# control.net
KiCad netlist of a schematic drawn in EAGLE
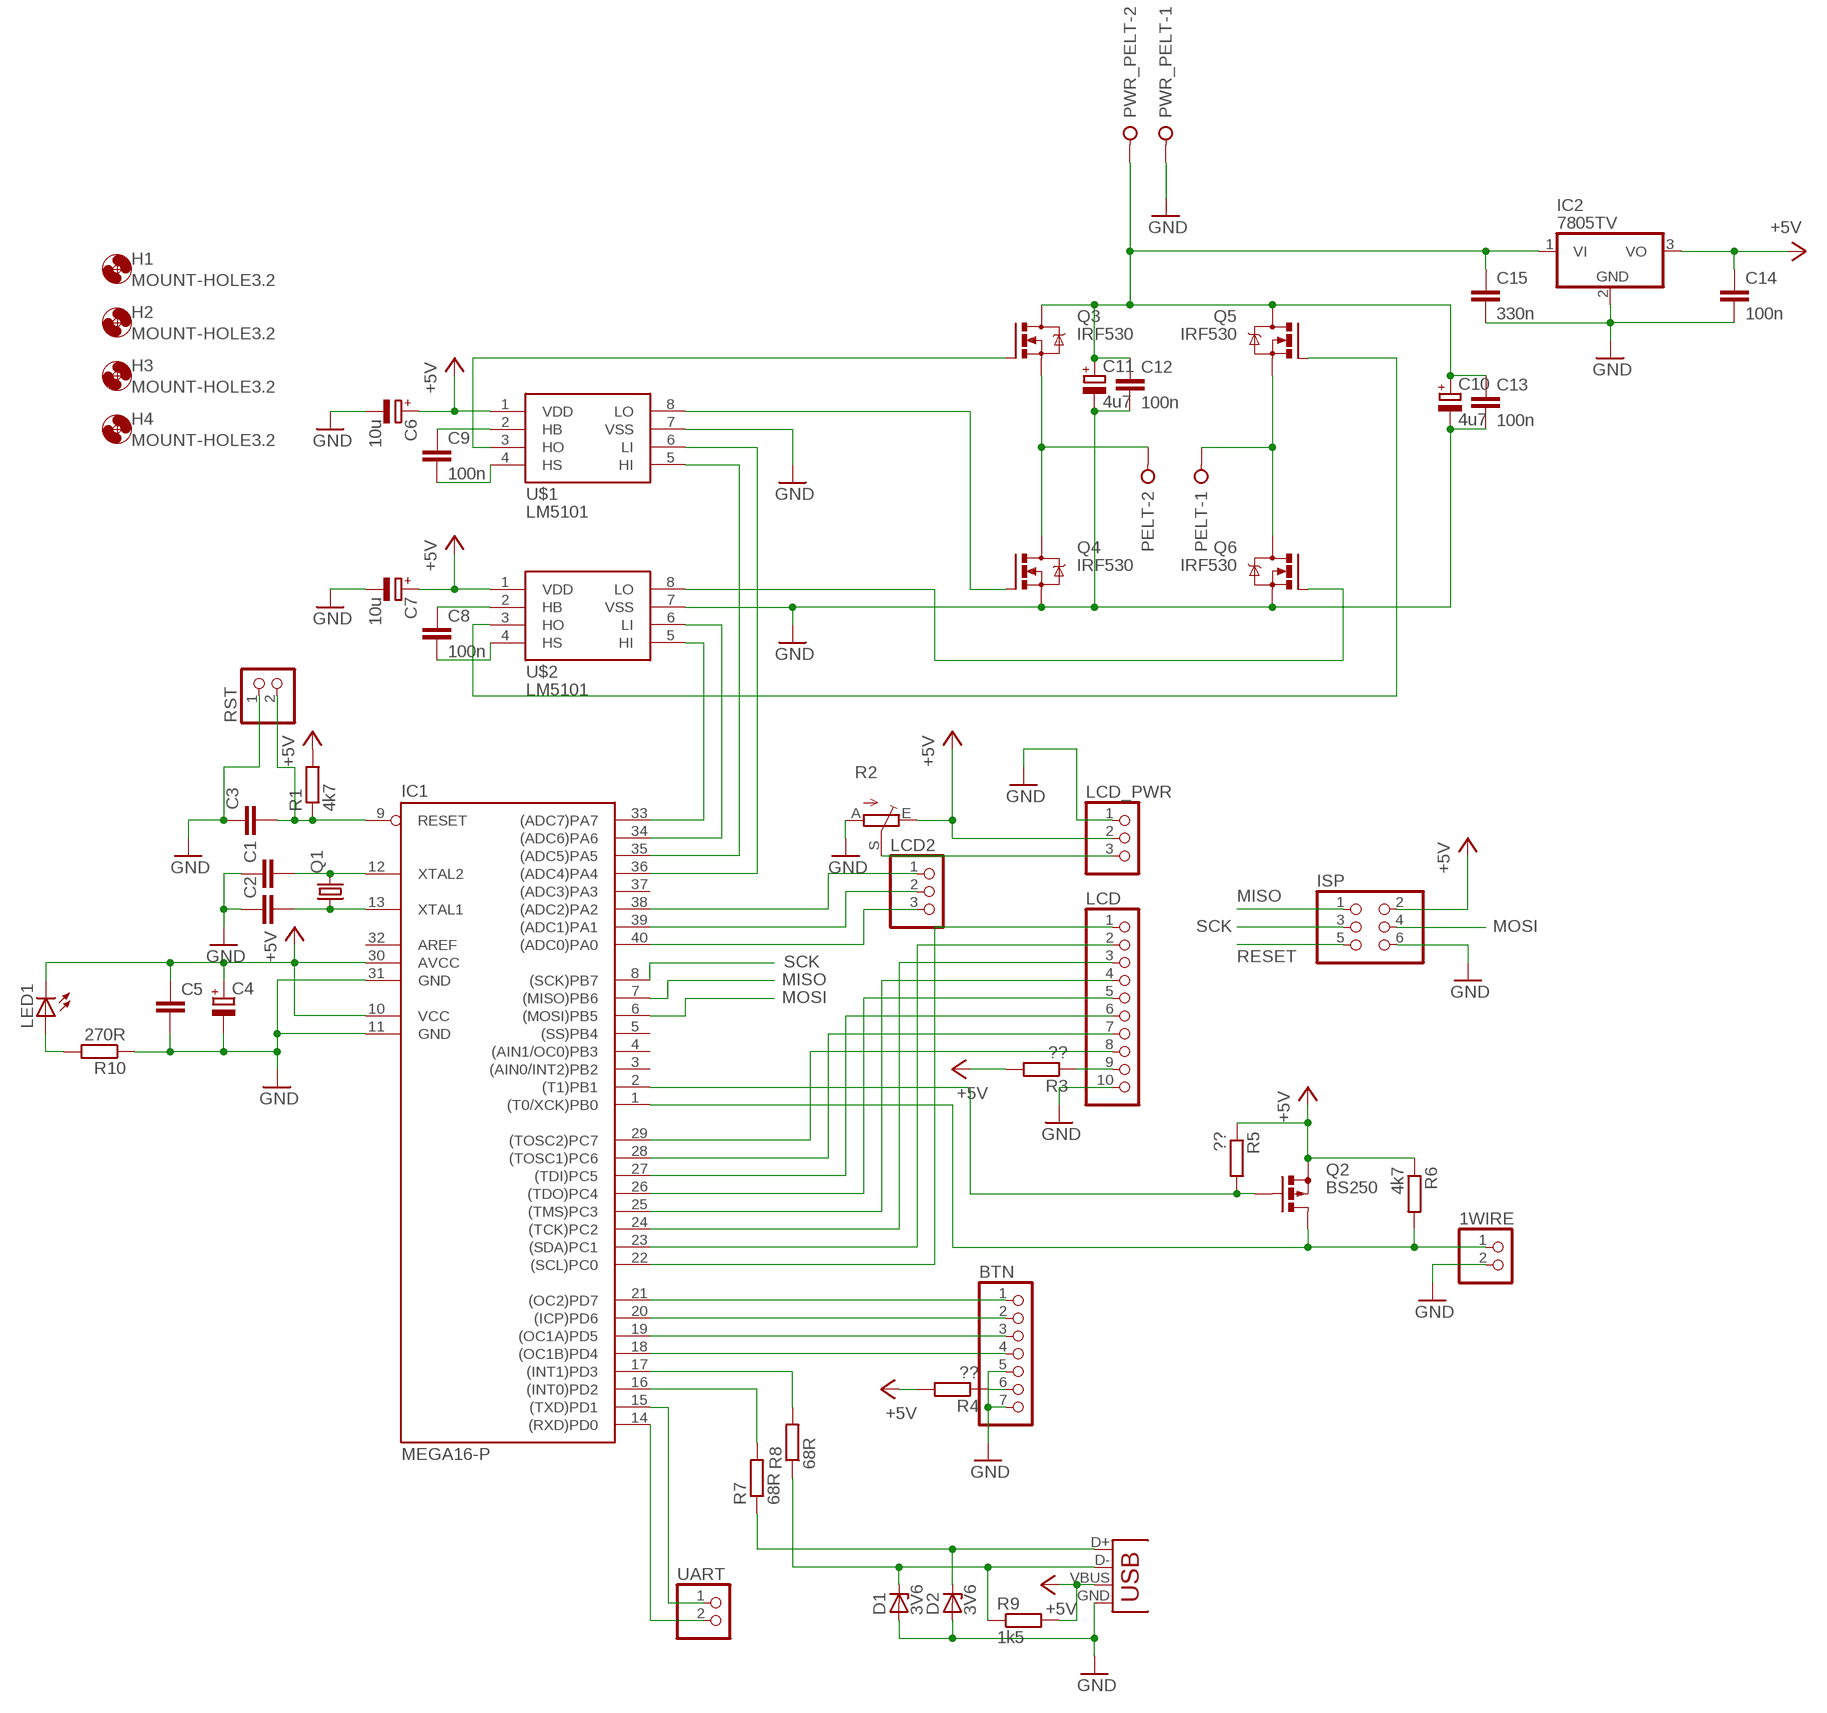
[diagram p0: schematic, sheet 1]

(export (version "E")
  (design (tool "Eeschema 10.0.6"))
  (components
    (comp (ref "1WIRE")
      (value "PINHD-1X2")
      (footprint "eagle-import:1X02")
      (libsource (lib "eagle-import") (part "PINHD-1X2"))
    )
    (comp (ref "BTN")
      (value "PINHD-1X7")
      (footprint "eagle-import:1X07")
      (libsource (lib "eagle-import") (part "PINHD-1X7"))
    )
    (comp (ref "C1")
      (value "C-EU025-025X050")
      (footprint "eagle-import:C025-025X050")
      (libsource (lib "eagle-import") (part "C-EU025-025X050"))
    )
    (comp (ref "C2")
      (value "C-EU025-025X050")
      (footprint "eagle-import:C025-025X050")
      (libsource (lib "eagle-import") (part "C-EU025-025X050"))
    )
    (comp (ref "C3")
      (value "C-EU050-024X044")
      (footprint "eagle-import:C050-024X044")
      (libsource (lib "eagle-import") (part "C-EU050-024X044"))
    )
    (comp (ref "C4")
      (value "CPOL-EUE2.5-5")
      (footprint "eagle-import:E2,5-5")
      (libsource (lib "eagle-import") (part "CPOL-EUE2.5-5"))
    )
    (comp (ref "C5")
      (value "C-EU050-024X044")
      (footprint "eagle-import:C050-024X044")
      (libsource (lib "eagle-import") (part "C-EU050-024X044"))
    )
    (comp (ref "C6")
      (value "10u")
      (footprint "eagle-import:E2,5-5")
      (libsource (lib "eagle-import") (part "CPOL-EUE2.5-5"))
    )
    (comp (ref "C7")
      (value "10u")
      (footprint "eagle-import:E2,5-5")
      (libsource (lib "eagle-import") (part "CPOL-EUE2.5-5"))
    )
    (comp (ref "C8")
      (value "100n")
      (footprint "eagle-import:C025-025X050")
      (libsource (lib "eagle-import") (part "C-EU025-025X050"))
    )
    (comp (ref "C9")
      (value "100n")
      (footprint "eagle-import:C025-025X050")
      (libsource (lib "eagle-import") (part "C-EU025-025X050"))
    )
    (comp (ref "C10")
      (value "4u7")
      (footprint "eagle-import:E5-5")
      (libsource (lib "eagle-import") (part "CPOL-EUE5-5"))
    )
    (comp (ref "C11")
      (value "4u7")
      (footprint "eagle-import:E5-5")
      (libsource (lib "eagle-import") (part "CPOL-EUE5-5"))
    )
    (comp (ref "C12")
      (value "100n")
      (footprint "eagle-import:C025-025X050")
      (libsource (lib "eagle-import") (part "C-EU025-025X050"))
    )
    (comp (ref "C13")
      (value "100n")
      (footprint "eagle-import:C025-025X050")
      (libsource (lib "eagle-import") (part "C-EU025-025X050"))
    )
    (comp (ref "C14")
      (value "100n")
      (footprint "eagle-import:C025-025X050")
      (libsource (lib "eagle-import") (part "C-EU025-025X050"))
    )
    (comp (ref "C15")
      (value "330n")
      (footprint "eagle-import:C025-025X050")
      (libsource (lib "eagle-import") (part "C-EU025-025X050"))
    )
    (comp (ref "D1")
      (value "3V6")
      (footprint "eagle-import:ZDIO-7.5")
      (libsource (lib "eagle-import") (part "ZENER-DIODEZD-7.5"))
    )
    (comp (ref "D2")
      (value "3V6")
      (footprint "eagle-import:ZDIO-7.5")
      (libsource (lib "eagle-import") (part "ZENER-DIODEZD-7.5"))
    )
    (comp (ref "H1")
      (value "MOUNT-HOLE3.2")
      (footprint "eagle-import:3,2")
      (libsource (lib "eagle-import") (part "MOUNT-HOLE3.2"))
    )
    (comp (ref "H2")
      (value "MOUNT-HOLE3.2")
      (footprint "eagle-import:3,2")
      (libsource (lib "eagle-import") (part "MOUNT-HOLE3.2"))
    )
    (comp (ref "H3")
      (value "MOUNT-HOLE3.2")
      (footprint "eagle-import:3,2")
      (libsource (lib "eagle-import") (part "MOUNT-HOLE3.2"))
    )
    (comp (ref "H4")
      (value "MOUNT-HOLE3.2")
      (footprint "eagle-import:3,2")
      (libsource (lib "eagle-import") (part "MOUNT-HOLE3.2"))
    )
    (comp (ref "IC1")
      (value "MEGA16-P")
      (footprint "eagle-import:DIL40")
      (fields (field (name "MPN") "ATMEGA16-16PU"))
      (libsource (lib "eagle-import") (part "MEGA16-P"))
    )
    (comp (ref "IC2")
      (value "7805TV")
      (footprint "eagle-import:TO220V")
      (libsource (lib "eagle-import") (part "78TV05"))
    )
    (comp (ref "ISP")
      (value "PINHD-2X3")
      (footprint "eagle-import:2X03")
      (libsource (lib "eagle-import") (part "PINHD-2X3"))
    )
    (comp (ref "LCD")
      (value "PINHD-1X10")
      (footprint "eagle-import:1X10")
      (libsource (lib "eagle-import") (part "PINHD-1X10"))
    )
    (comp (ref "LCD2")
      (value "PINHD-1X3")
      (footprint "eagle-import:1X03")
      (libsource (lib "eagle-import") (part "PINHD-1X3"))
    )
    (comp (ref "LCD_PWR")
      (value "PINHD-1X3")
      (footprint "eagle-import:1X03")
      (libsource (lib "eagle-import") (part "PINHD-1X3"))
    )
    (comp (ref "LED1")
      (value "LED3MM")
      (footprint "eagle-import:LED3MM")
      (libsource (lib "eagle-import") (part "LED3MM"))
    )
    (comp (ref "PELT")
      (value "W237-02P")
      (footprint "eagle-import:W237-132")
      (libsource (lib "eagle-import") (part "W237-02P"))
    )
    (comp (ref "PWR_PELT")
      (value "W237-02P")
      (footprint "eagle-import:W237-132")
      (fields (field (name "OC_FARNELL") "unknown") (field (name "OC_NEWARK") "unknown"))
      (libsource (lib "eagle-import") (part "W237-02P"))
    )
    (comp (ref "Q1")
      (value "CRYSTALHC49U-V")
      (footprint "eagle-import:HC49U-V")
      (libsource (lib "eagle-import") (part "CRYSTALHC49U-V"))
    )
    (comp (ref "Q2")
      (value "BS250")
      (footprint "eagle-import:SOT54E")
      (libsource (lib "eagle-import") (part "BS250"))
    )
    (comp (ref "Q3")
      (value "IRF530")
      (footprint "eagle-import:TO220BV")
      (libsource (lib "eagle-import") (part "IRF530"))
    )
    (comp (ref "Q4")
      (value "IRF530")
      (footprint "eagle-import:TO220BV")
      (libsource (lib "eagle-import") (part "IRF530"))
    )
    (comp (ref "Q5")
      (value "IRF530")
      (footprint "eagle-import:TO220BV")
      (libsource (lib "eagle-import") (part "IRF530"))
    )
    (comp (ref "Q6")
      (value "IRF530")
      (footprint "eagle-import:TO220BV")
      (libsource (lib "eagle-import") (part "IRF530"))
    )
    (comp (ref "R1")
      (value "4k7")
      (footprint "eagle-import:0207_10")
      (libsource (lib "eagle-import") (part "R-EU_0207/10"))
    )
    (comp (ref "R2")
      (value "TRIM_EU-LI10")
      (footprint "eagle-import:LI10")
      (libsource (lib "eagle-import") (part "TRIM_EU-LI10"))
    )
    (comp (ref "R3")
      (value "??")
      (footprint "eagle-import:0207_10")
      (libsource (lib "eagle-import") (part "R-EU_0207/10"))
    )
    (comp (ref "R4")
      (value "??")
      (footprint "eagle-import:0207_10")
      (libsource (lib "eagle-import") (part "R-EU_0207/10"))
    )
    (comp (ref "R5")
      (value "??")
      (footprint "eagle-import:0207_10")
      (libsource (lib "eagle-import") (part "R-EU_0207/10"))
    )
    (comp (ref "R6")
      (value "4k7")
      (footprint "eagle-import:0207_10")
      (libsource (lib "eagle-import") (part "R-EU_0207/10"))
    )
    (comp (ref "R7")
      (value "68R")
      (footprint "eagle-import:0207_10")
      (libsource (lib "eagle-import") (part "R-EU_0207/10"))
    )
    (comp (ref "R8")
      (value "68R")
      (footprint "eagle-import:0207_10")
      (libsource (lib "eagle-import") (part "R-EU_0207/10"))
    )
    (comp (ref "R9")
      (value "1k5")
      (footprint "eagle-import:0207_10")
      (libsource (lib "eagle-import") (part "R-EU_0207/10"))
    )
    (comp (ref "R10")
      (value "270R")
      (footprint "eagle-import:0207_10")
      (libsource (lib "eagle-import") (part "R-EU_0207/10"))
    )
    (comp (ref "RST")
      (value "PINHD-1X2")
      (footprint "eagle-import:1X02")
      (libsource (lib "eagle-import") (part "PINHD-1X2"))
    )
    (comp (ref "U$1")
      (value "LM5101")
      (footprint "eagle-import:SOIC8")
      (libsource (lib "eagle-import") (part "LM5101"))
    )
    (comp (ref "U$2")
      (value "LM5101")
      (footprint "eagle-import:SOIC8")
      (libsource (lib "eagle-import") (part "LM5101"))
    )
    (comp (ref "UART")
      (value "PINHD-1X2")
      (footprint "eagle-import:1X02")
      (libsource (lib "eagle-import") (part "PINHD-1X2"))
    )
    (comp (ref "X1")
      (value "USBPTH")
      (footprint "eagle-import:USB-B-PTH")
      (libsource (lib "eagle-import") (part "USBPTH"))
    )
  )
  (nets
    (net (code "1") (name "+5V") (class "Default")
      (node (ref "C14") (pin "1") (pinfunction "1_1") (pintype "passive"))
      (node (ref "C4") (pin "+") (pinfunction "+_+") (pintype "passive"))
      (node (ref "C5") (pin "1") (pinfunction "1_1") (pintype "passive"))
      (node (ref "C6") (pin "+") (pinfunction "+_+") (pintype "passive"))
      (node (ref "C7") (pin "+") (pinfunction "+_+") (pintype "passive"))
      (node (ref "IC1") (pin "10") (pinfunction "VCC_10") (pintype "power_in"))
      (node (ref "IC1") (pin "30") (pinfunction "AVCC_30") (pintype "power_in"))
      (node (ref "IC2") (pin "3") (pinfunction "VO_3") (pintype "passive"))
      (node (ref "ISP") (pin "2") (pinfunction "2_2") (pintype "passive"))
      (node (ref "LCD_PWR") (pin "2") (pinfunction "2_2") (pintype "passive"))
      (node (ref "LED1") (pin "K") (pinfunction "C_K") (pintype "passive"))
      (node (ref "Q2") (pin "S") (pinfunction "S_S") (pintype "passive"))
      (node (ref "R1") (pin "2") (pinfunction "2_2") (pintype "passive"))
      (node (ref "R2") (pin "E") (pinfunction "E_E") (pintype "passive"))
      (node (ref "R3") (pin "2") (pinfunction "2_2") (pintype "passive"))
      (node (ref "R4") (pin "2") (pinfunction "2_2") (pintype "passive"))
      (node (ref "R5") (pin "1") (pinfunction "1_1") (pintype "passive"))
      (node (ref "R6") (pin "1") (pinfunction "1_1") (pintype "passive"))
      (node (ref "R9") (pin "2") (pinfunction "2_2") (pintype "passive"))
      (node (ref "U$1") (pin "1") (pinfunction "VDD_1") (pintype "bidirectional"))
      (node (ref "U$2") (pin "1") (pinfunction "VDD_1") (pintype "bidirectional"))
      (node (ref "X1") (pin "VBUS") (pinfunction "VBUS_VBUS") (pintype "bidirectional"))
    )
    (net (code "2") (name "/MISO") (class "Default")
      (node (ref "IC1") (pin "7") (pinfunction "(MISO)PB6_7") (pintype "bidirectional"))
      (node (ref "ISP") (pin "1") (pinfunction "1_1") (pintype "passive"))
    )
    (net (code "3") (name "/MOSI") (class "Default")
      (node (ref "IC1") (pin "6") (pinfunction "(MOSI)PB5_6") (pintype "bidirectional"))
      (node (ref "ISP") (pin "4") (pinfunction "4_4") (pintype "passive"))
    )
    (net (code "4") (name "/RESET") (class "Default")
      (node (ref "C3") (pin "2") (pinfunction "2_2") (pintype "passive"))
      (node (ref "IC1") (pin "9") (pinfunction "RESET_9") (pintype "input"))
      (node (ref "ISP") (pin "5") (pinfunction "5_5") (pintype "passive"))
      (node (ref "R1") (pin "1") (pinfunction "1_1") (pintype "passive"))
      (node (ref "RST") (pin "2") (pinfunction "2_2") (pintype "passive"))
    )
    (net (code "5") (name "/SCK") (class "Default")
      (node (ref "IC1") (pin "8") (pinfunction "(SCK)PB7_8") (pintype "bidirectional"))
      (node (ref "ISP") (pin "3") (pinfunction "3_3") (pintype "passive"))
    )
    (net (code "6") (name "GND") (class "Default")
      (node (ref "1WIRE") (pin "2") (pinfunction "2_2") (pintype "passive"))
      (node (ref "BTN") (pin "5") (pinfunction "5_5") (pintype "passive"))
      (node (ref "BTN") (pin "7") (pinfunction "7_7") (pintype "passive"))
      (node (ref "C1") (pin "1") (pinfunction "1_1") (pintype "passive"))
      (node (ref "C10") (pin "-") (pinfunction "-_-") (pintype "passive"))
      (node (ref "C11") (pin "-") (pinfunction "-_-") (pintype "passive"))
      (node (ref "C12") (pin "2") (pinfunction "2_2") (pintype "passive"))
      (node (ref "C13") (pin "2") (pinfunction "2_2") (pintype "passive"))
      (node (ref "C14") (pin "2") (pinfunction "2_2") (pintype "passive"))
      (node (ref "C15") (pin "2") (pinfunction "2_2") (pintype "passive"))
      (node (ref "C2") (pin "1") (pinfunction "1_1") (pintype "passive"))
      (node (ref "C3") (pin "1") (pinfunction "1_1") (pintype "passive"))
      (node (ref "C4") (pin "-") (pinfunction "-_-") (pintype "passive"))
      (node (ref "C5") (pin "2") (pinfunction "2_2") (pintype "passive"))
      (node (ref "C6") (pin "-") (pinfunction "-_-") (pintype "passive"))
      (node (ref "C7") (pin "-") (pinfunction "-_-") (pintype "passive"))
      (node (ref "D1") (pin "A") (pinfunction "A_A") (pintype "passive"))
      (node (ref "D2") (pin "A") (pinfunction "A_A") (pintype "passive"))
      (node (ref "IC1") (pin "11") (pinfunction "GND_11") (pintype "power_in"))
      (node (ref "IC1") (pin "31") (pinfunction "GND_31") (pintype "power_in"))
      (node (ref "IC2") (pin "2") (pinfunction "GND_2") (pintype "passive"))
      (node (ref "ISP") (pin "6") (pinfunction "6_6") (pintype "passive"))
      (node (ref "LCD") (pin "10") (pinfunction "10_10") (pintype "passive"))
      (node (ref "LCD_PWR") (pin "1") (pinfunction "1_1") (pintype "passive"))
      (node (ref "PWR_PELT") (pin "1") (pinfunction "KL_1") (pintype "passive"))
      (node (ref "Q4") (pin "S") (pinfunction "S_S") (pintype "passive"))
      (node (ref "Q6") (pin "S") (pinfunction "S_S") (pintype "passive"))
      (node (ref "R10") (pin "1") (pinfunction "1_1") (pintype "passive"))
      (node (ref "R2") (pin "A") (pinfunction "A_A") (pintype "passive"))
      (node (ref "RST") (pin "1") (pinfunction "1_1") (pintype "passive"))
      (node (ref "U$1") (pin "7") (pinfunction "VSS_7") (pintype "bidirectional"))
      (node (ref "U$2") (pin "7") (pinfunction "VSS_7") (pintype "bidirectional"))
      (node (ref "X1") (pin "GND") (pinfunction "GND_GND") (pintype "bidirectional"))
    )
    (net (code "7") (name "Net-(BTN-Pad6)") (class "Default")
      (node (ref "BTN") (pin "6") (pinfunction "6_6") (pintype "passive"))
      (node (ref "R4") (pin "1") (pinfunction "1_1") (pintype "passive"))
    )
    (net (code "8") (name "Net-(D1-PadC)") (class "Default")
      (node (ref "D1") (pin "C") (pinfunction "C_C") (pintype "passive"))
      (node (ref "R8") (pin "1") (pinfunction "1_1") (pintype "passive"))
      (node (ref "R9") (pin "1") (pinfunction "1_1") (pintype "passive"))
      (node (ref "X1") (pin "D-") (pinfunction "D-_D-") (pintype "bidirectional"))
    )
    (net (code "9") (name "Net-(D2-PadC)") (class "Default")
      (node (ref "D2") (pin "C") (pinfunction "C_C") (pintype "passive"))
      (node (ref "R7") (pin "1") (pinfunction "1_1") (pintype "passive"))
      (node (ref "X1") (pin "D+") (pinfunction "D+_D+") (pintype "bidirectional"))
    )
    (net (code "10") (name "Net-(IC1-(ADC0)PA0)") (class "Default")
      (node (ref "IC1") (pin "40") (pinfunction "(ADC0)PA0_40") (pintype "bidirectional"))
      (node (ref "LCD2") (pin "3") (pinfunction "3_3") (pintype "passive"))
    )
    (net (code "11") (name "Net-(IC1-(ADC1)PA1)") (class "Default")
      (node (ref "IC1") (pin "39") (pinfunction "(ADC1)PA1_39") (pintype "bidirectional"))
      (node (ref "LCD2") (pin "2") (pinfunction "2_2") (pintype "passive"))
    )
    (net (code "12") (name "Net-(IC1-(ADC2)PA2)") (class "Default")
      (node (ref "IC1") (pin "38") (pinfunction "(ADC2)PA2_38") (pintype "bidirectional"))
      (node (ref "LCD2") (pin "1") (pinfunction "1_1") (pintype "passive"))
    )
    (net (code "13") (name "Net-(IC1-(ADC4)PA4)") (class "Default")
      (node (ref "IC1") (pin "36") (pinfunction "(ADC4)PA4_36") (pintype "bidirectional"))
      (node (ref "U$1") (pin "6") (pinfunction "LI_6") (pintype "bidirectional"))
    )
    (net (code "14") (name "Net-(IC1-(ADC5)PA5)") (class "Default")
      (node (ref "IC1") (pin "35") (pinfunction "(ADC5)PA5_35") (pintype "bidirectional"))
      (node (ref "U$1") (pin "5") (pinfunction "HI_5") (pintype "bidirectional"))
    )
    (net (code "15") (name "Net-(IC1-(ADC6)PA6)") (class "Default")
      (node (ref "IC1") (pin "34") (pinfunction "(ADC6)PA6_34") (pintype "bidirectional"))
      (node (ref "U$2") (pin "6") (pinfunction "LI_6") (pintype "bidirectional"))
    )
    (net (code "16") (name "Net-(IC1-(ADC7)PA7)") (class "Default")
      (node (ref "IC1") (pin "33") (pinfunction "(ADC7)PA7_33") (pintype "bidirectional"))
      (node (ref "U$2") (pin "5") (pinfunction "HI_5") (pintype "bidirectional"))
    )
    (net (code "17") (name "Net-(IC1-(ICP)PD6)") (class "Default")
      (node (ref "BTN") (pin "2") (pinfunction "2_2") (pintype "passive"))
      (node (ref "IC1") (pin "20") (pinfunction "(ICP)PD6_20") (pintype "bidirectional"))
    )
    (net (code "18") (name "Net-(IC1-(INT0)PD2)") (class "Default")
      (node (ref "IC1") (pin "16") (pinfunction "(INT0)PD2_16") (pintype "bidirectional"))
      (node (ref "R7") (pin "2") (pinfunction "2_2") (pintype "passive"))
    )
    (net (code "19") (name "Net-(IC1-(INT1)PD3)") (class "Default")
      (node (ref "IC1") (pin "17") (pinfunction "(INT1)PD3_17") (pintype "bidirectional"))
      (node (ref "R8") (pin "2") (pinfunction "2_2") (pintype "passive"))
    )
    (net (code "20") (name "Net-(IC1-(OC1A)PD5)") (class "Default")
      (node (ref "BTN") (pin "3") (pinfunction "3_3") (pintype "passive"))
      (node (ref "IC1") (pin "19") (pinfunction "(OC1A)PD5_19") (pintype "bidirectional"))
    )
    (net (code "21") (name "Net-(IC1-(OC1B)PD4)") (class "Default")
      (node (ref "BTN") (pin "4") (pinfunction "4_4") (pintype "passive"))
      (node (ref "IC1") (pin "18") (pinfunction "(OC1B)PD4_18") (pintype "bidirectional"))
    )
    (net (code "22") (name "Net-(IC1-(OC2)PD7)") (class "Default")
      (node (ref "BTN") (pin "1") (pinfunction "1_1") (pintype "passive"))
      (node (ref "IC1") (pin "21") (pinfunction "(OC2)PD7_21") (pintype "bidirectional"))
    )
    (net (code "23") (name "Net-(IC1-(RXD)PD0)") (class "Default")
      (node (ref "IC1") (pin "14") (pinfunction "(RXD)PD0_14") (pintype "bidirectional"))
      (node (ref "UART") (pin "2") (pinfunction "2_2") (pintype "passive"))
    )
    (net (code "24") (name "Net-(IC1-(SCL)PC0)") (class "Default")
      (node (ref "IC1") (pin "22") (pinfunction "(SCL)PC0_22") (pintype "bidirectional"))
      (node (ref "LCD") (pin "1") (pinfunction "1_1") (pintype "passive"))
    )
    (net (code "25") (name "Net-(IC1-(SDA)PC1)") (class "Default")
      (node (ref "IC1") (pin "23") (pinfunction "(SDA)PC1_23") (pintype "bidirectional"))
      (node (ref "LCD") (pin "2") (pinfunction "2_2") (pintype "passive"))
    )
    (net (code "26") (name "Net-(IC1-(T0{slash}XCK)PB0)") (class "Default")
      (node (ref "1WIRE") (pin "1") (pinfunction "1_1") (pintype "passive"))
      (node (ref "IC1") (pin "1") (pinfunction "(T0/XCK)PB0_1") (pintype "bidirectional"))
      (node (ref "Q2") (pin "D") (pinfunction "D_D") (pintype "passive"))
      (node (ref "R6") (pin "2") (pinfunction "2_2") (pintype "passive"))
    )
    (net (code "27") (name "Net-(IC1-(T1)PB1)") (class "Default")
      (node (ref "IC1") (pin "2") (pinfunction "(T1)PB1_2") (pintype "bidirectional"))
      (node (ref "Q2") (pin "G") (pinfunction "G_G") (pintype "passive"))
      (node (ref "R5") (pin "2") (pinfunction "2_2") (pintype "passive"))
    )
    (net (code "28") (name "Net-(IC1-(TCK)PC2)") (class "Default")
      (node (ref "IC1") (pin "24") (pinfunction "(TCK)PC2_24") (pintype "bidirectional"))
      (node (ref "LCD") (pin "3") (pinfunction "3_3") (pintype "passive"))
    )
    (net (code "29") (name "Net-(IC1-(TDI)PC5)") (class "Default")
      (node (ref "IC1") (pin "27") (pinfunction "(TDI)PC5_27") (pintype "bidirectional"))
      (node (ref "LCD") (pin "6") (pinfunction "6_6") (pintype "passive"))
    )
    (net (code "30") (name "Net-(IC1-(TDO)PC4)") (class "Default")
      (node (ref "IC1") (pin "26") (pinfunction "(TDO)PC4_26") (pintype "bidirectional"))
      (node (ref "LCD") (pin "5") (pinfunction "5_5") (pintype "passive"))
    )
    (net (code "31") (name "Net-(IC1-(TMS)PC3)") (class "Default")
      (node (ref "IC1") (pin "25") (pinfunction "(TMS)PC3_25") (pintype "bidirectional"))
      (node (ref "LCD") (pin "4") (pinfunction "4_4") (pintype "passive"))
    )
    (net (code "32") (name "Net-(IC1-(TOSC1)PC6)") (class "Default")
      (node (ref "IC1") (pin "28") (pinfunction "(TOSC1)PC6_28") (pintype "bidirectional"))
      (node (ref "LCD") (pin "7") (pinfunction "7_7") (pintype "passive"))
    )
    (net (code "33") (name "Net-(IC1-(TOSC2)PC7)") (class "Default")
      (node (ref "IC1") (pin "29") (pinfunction "(TOSC2)PC7_29") (pintype "bidirectional"))
      (node (ref "LCD") (pin "8") (pinfunction "8_8") (pintype "passive"))
    )
    (net (code "34") (name "Net-(IC1-(TXD)PD1)") (class "Default")
      (node (ref "IC1") (pin "15") (pinfunction "(TXD)PD1_15") (pintype "bidirectional"))
      (node (ref "UART") (pin "1") (pinfunction "1_1") (pintype "passive"))
    )
    (net (code "35") (name "Net-(IC1-XTAL1)") (class "Default")
      (node (ref "C2") (pin "2") (pinfunction "2_2") (pintype "passive"))
      (node (ref "IC1") (pin "13") (pinfunction "XTAL1_13") (pintype "bidirectional"))
      (node (ref "Q1") (pin "1") (pinfunction "1_1") (pintype "passive"))
    )
    (net (code "36") (name "Net-(IC1-XTAL2)") (class "Default")
      (node (ref "C1") (pin "2") (pinfunction "2_2") (pintype "passive"))
      (node (ref "IC1") (pin "12") (pinfunction "XTAL2_12") (pintype "bidirectional"))
      (node (ref "Q1") (pin "2") (pinfunction "2_2") (pintype "passive"))
    )
    (net (code "37") (name "Net-(IC2-VI)") (class "Default")
      (node (ref "C10") (pin "+") (pinfunction "+_+") (pintype "passive"))
      (node (ref "C11") (pin "+") (pinfunction "+_+") (pintype "passive"))
      (node (ref "C12") (pin "1") (pinfunction "1_1") (pintype "passive"))
      (node (ref "C13") (pin "1") (pinfunction "1_1") (pintype "passive"))
      (node (ref "C15") (pin "1") (pinfunction "1_1") (pintype "passive"))
      (node (ref "IC2") (pin "1") (pinfunction "VI_1") (pintype "input"))
      (node (ref "PWR_PELT") (pin "2") (pinfunction "KL_2") (pintype "passive"))
      (node (ref "Q3") (pin "D") (pinfunction "D_D") (pintype "passive"))
      (node (ref "Q5") (pin "D") (pinfunction "D_D") (pintype "passive"))
    )
    (net (code "38") (name "Net-(LCD-Pad9)") (class "Default")
      (node (ref "LCD") (pin "9") (pinfunction "9_9") (pintype "passive"))
      (node (ref "R3") (pin "1") (pinfunction "1_1") (pintype "passive"))
    )
    (net (code "39") (name "Net-(LCD_PWR-Pad3)") (class "Default")
      (node (ref "LCD_PWR") (pin "3") (pinfunction "3_3") (pintype "passive"))
      (node (ref "R2") (pin "S") (pinfunction "S_S") (pintype "passive"))
    )
    (net (code "40") (name "Net-(LED1-PadA)") (class "Default")
      (node (ref "LED1") (pin "A") (pinfunction "A_A") (pintype "passive"))
      (node (ref "R10") (pin "2") (pinfunction "2_2") (pintype "passive"))
    )
    (net (code "41") (name "Net-(PELTA-KL)") (class "Default")
      (node (ref "PELT") (pin "1") (pinfunction "KL_1") (pintype "passive"))
      (node (ref "Q5") (pin "S") (pinfunction "S_S") (pintype "passive"))
      (node (ref "Q6") (pin "D") (pinfunction "D_D") (pintype "passive"))
    )
    (net (code "42") (name "Net-(PELTB-KL)") (class "Default")
      (node (ref "PELT") (pin "2") (pinfunction "KL_2") (pintype "passive"))
      (node (ref "Q3") (pin "S") (pinfunction "S_S") (pintype "passive"))
      (node (ref "Q4") (pin "D") (pinfunction "D_D") (pintype "passive"))
    )
    (net (code "43") (name "Net-(U$1-HB)") (class "Default")
      (node (ref "C9") (pin "1") (pinfunction "1_1") (pintype "passive"))
      (node (ref "U$1") (pin "2") (pinfunction "HB_2") (pintype "bidirectional"))
    )
    (net (code "44") (name "Net-(U$1-HO)") (class "Default")
      (node (ref "Q3") (pin "G") (pinfunction "G_G") (pintype "passive"))
      (node (ref "U$1") (pin "3") (pinfunction "HO_3") (pintype "bidirectional"))
    )
    (net (code "45") (name "Net-(U$1-HS)") (class "Default")
      (node (ref "C9") (pin "2") (pinfunction "2_2") (pintype "passive"))
      (node (ref "U$1") (pin "4") (pinfunction "HS_4") (pintype "bidirectional"))
    )
    (net (code "46") (name "Net-(U$1-LO)") (class "Default")
      (node (ref "Q4") (pin "G") (pinfunction "G_G") (pintype "passive"))
      (node (ref "U$1") (pin "8") (pinfunction "LO_8") (pintype "bidirectional"))
    )
    (net (code "47") (name "Net-(U$2-HB)") (class "Default")
      (node (ref "C8") (pin "1") (pinfunction "1_1") (pintype "passive"))
      (node (ref "U$2") (pin "2") (pinfunction "HB_2") (pintype "bidirectional"))
    )
    (net (code "48") (name "Net-(U$2-HO)") (class "Default")
      (node (ref "Q5") (pin "G") (pinfunction "G_G") (pintype "passive"))
      (node (ref "U$2") (pin "3") (pinfunction "HO_3") (pintype "bidirectional"))
    )
    (net (code "49") (name "Net-(U$2-HS)") (class "Default")
      (node (ref "C8") (pin "2") (pinfunction "2_2") (pintype "passive"))
      (node (ref "U$2") (pin "4") (pinfunction "HS_4") (pintype "bidirectional"))
    )
    (net (code "50") (name "Net-(U$2-LO)") (class "Default")
      (node (ref "Q6") (pin "G") (pinfunction "G_G") (pintype "passive"))
      (node (ref "U$2") (pin "8") (pinfunction "LO_8") (pintype "bidirectional"))
    )
    (net (code "51") (name "unconnected-(IC1-(ADC3)PA3-Pad37)") (class "Default")
      (node (ref "IC1") (pin "37") (pinfunction "(ADC3)PA3_37") (pintype "bidirectional"))
    )
    (net (code "52") (name "unconnected-(IC1-(AIN0{slash}INT2)PB2-Pad3)") (class "Default")
      (node (ref "IC1") (pin "3") (pinfunction "(AIN0/INT2)PB2_3") (pintype "bidirectional"))
    )
    (net (code "53") (name "unconnected-(IC1-(AIN1{slash}OC0)PB3-Pad4)") (class "Default")
      (node (ref "IC1") (pin "4") (pinfunction "(AIN1/OC0)PB3_4") (pintype "bidirectional"))
    )
    (net (code "54") (name "unconnected-(IC1-(SS)PB4-Pad5)") (class "Default")
      (node (ref "IC1") (pin "5") (pinfunction "(SS)PB4_5") (pintype "bidirectional"))
    )
    (net (code "55") (name "unconnected-(IC1-AREF-Pad32)") (class "Default")
      (node (ref "IC1") (pin "32") (pinfunction "AREF_32") (pintype "passive"))
    )
  )
)
